# lm3410-boost-flashlight-driver-17mm-mk-1.net
KiCad netlist of a schematic drawn in EAGLE
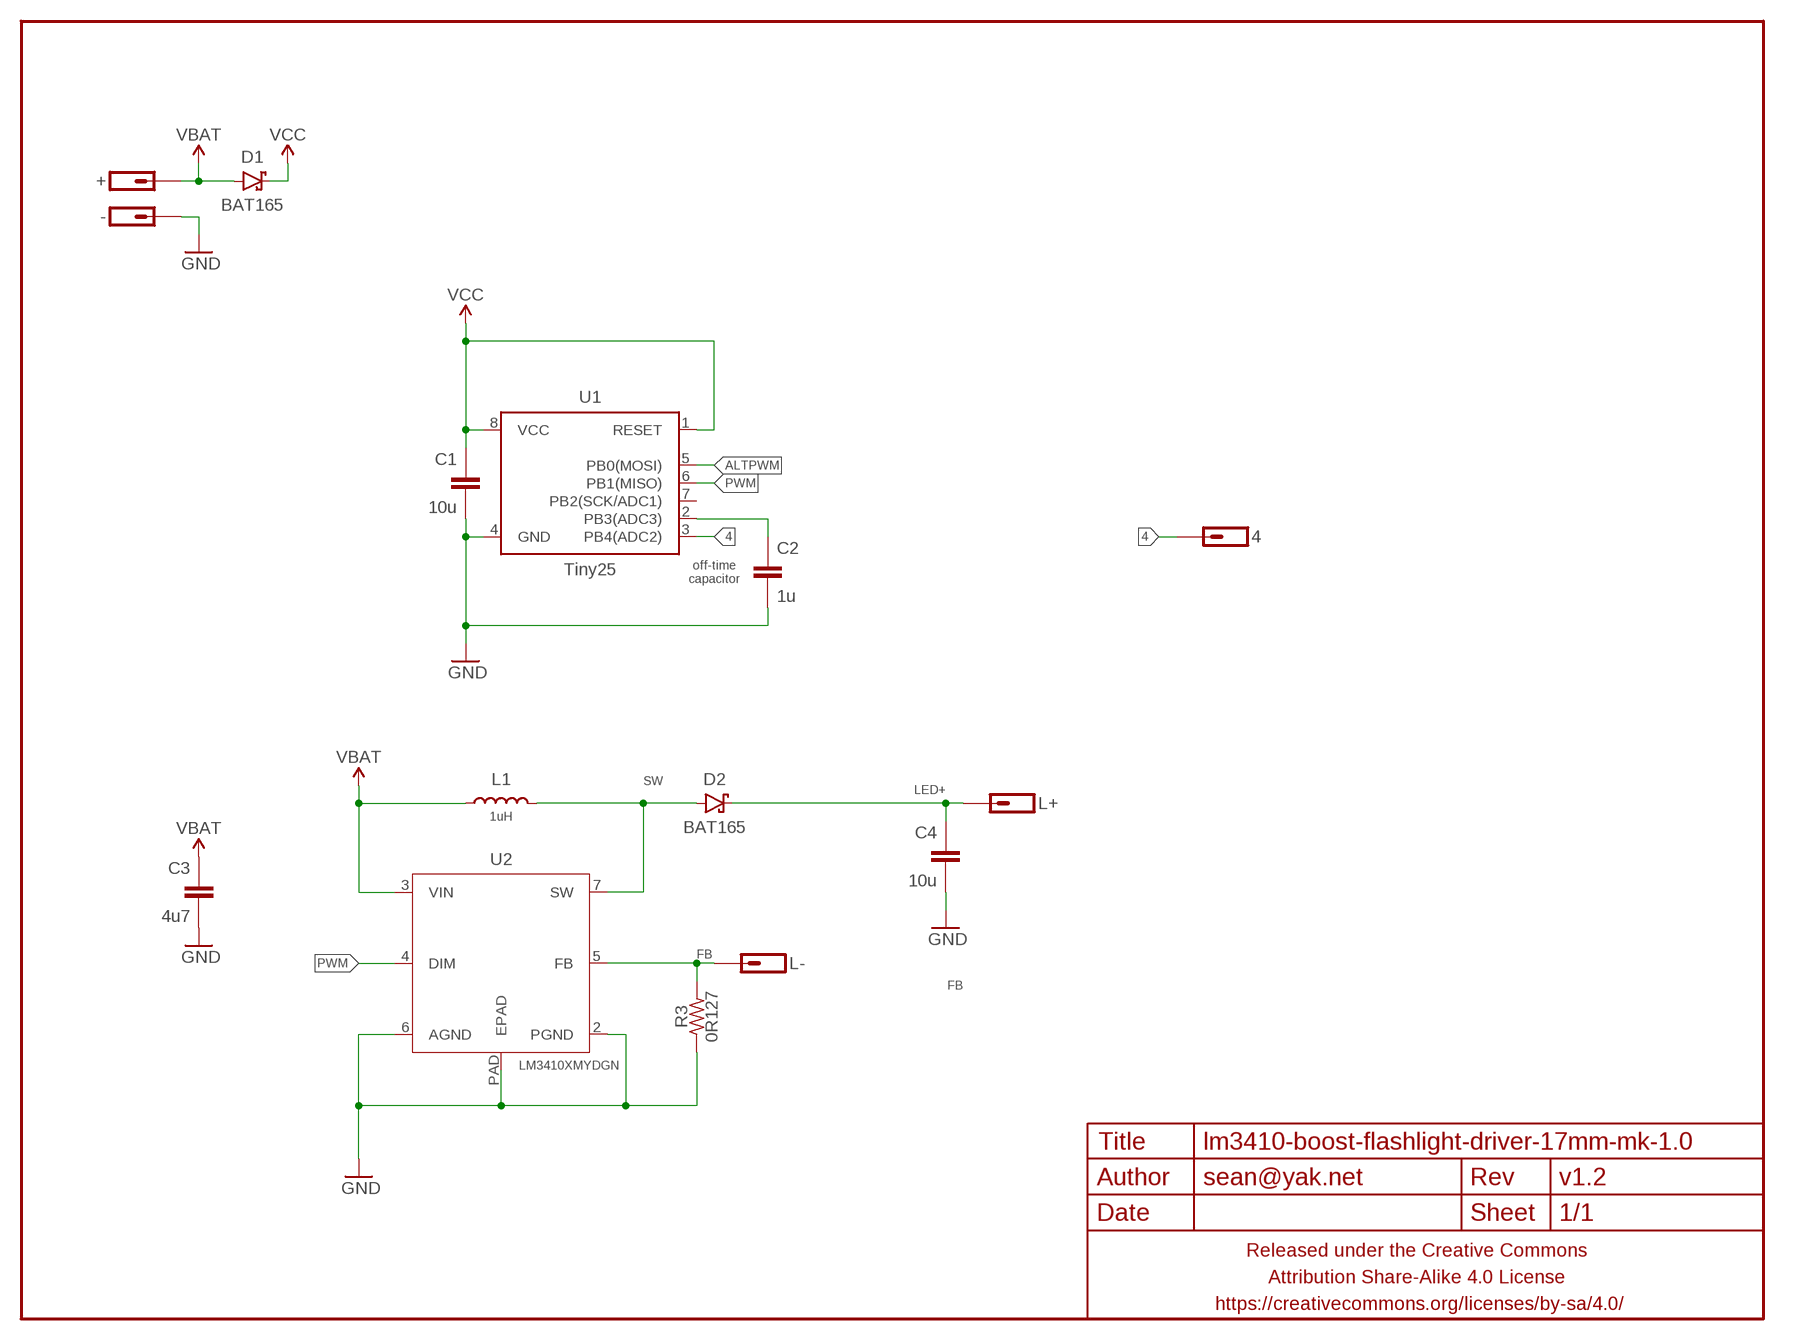
[diagram p0: schematic, sheet 1]

(export (version "E")
  (design (tool "Eeschema 10.0.6"))
  (components
    (comp (ref "+")
      (value "M01PTH-1MM-CIR-NS")
      (footprint "eagle-import:1X01-1MM-CIR-NS")
      (libsource (lib "eagle-import") (part "M01PTH-1MM-CIR-NS"))
    )
    (comp (ref "-")
      (value "M01NOT-A-VIA-NOPE")
      (footprint "eagle-import:1X01_NOSILK_NOSTOP")
      (libsource (lib "eagle-import") (part "M01NOT-A-VIA-NOPE"))
    )
    (comp (ref "4")
      (value "M01SMD-1MM-DIA-NS")
      (footprint "eagle-import:1X01-SMD-1MM-DIA-NS")
      (libsource (lib "eagle-import") (part "M01SMD-1MM-DIA-NS"))
    )
    (comp (ref "C1")
      (value "10u")
      (footprint "eagle-import:C0603-TIGHTER")
      (libsource (lib "eagle-import") (part "CAPACITOR-CERAMICC0603-TIGHTER"))
    )
    (comp (ref "C2")
      (value "1u")
      (footprint "eagle-import:C0603-TIGHTER")
      (libsource (lib "eagle-import") (part "CAPACITOR-CERAMICC0603-TIGHTER"))
    )
    (comp (ref "C3")
      (value "4u7")
      (footprint "eagle-import:C0603-TIGHTER")
      (libsource (lib "eagle-import") (part "CAPACITOR-CERAMICC0603-TIGHTER"))
    )
    (comp (ref "C4")
      (value "10u")
      (footprint "eagle-import:C0603-TIGHTER")
      (libsource (lib "eagle-import") (part "CAPACITOR-CERAMICC0603-TIGHTER"))
    )
    (comp (ref "D1")
      (value "BAT165")
      (footprint "eagle-import:SOD323-SCHOTTKY")
      (libsource (lib "eagle-import") (part "DIODE-SCHOTTKYSOD323"))
    )
    (comp (ref "D2")
      (value "BAT165")
      (footprint "eagle-import:SOD323-SCHOTTKY")
      (libsource (lib "eagle-import") (part "DIODE-SCHOTTKYSOD323"))
    )
    (comp (ref "FRAME1")
      (value "FRAME-LETTERNO_PACKAGE")
      (footprint "eagle-import:DUMMY")
      (fields (field (name "DESIGNER") "sean@yak.net") (field (name "VERSION") "v1.2"))
      (libsource (lib "eagle-import") (part "FRAME-LETTERNO_PACKAGE"))
    )
    (comp (ref "L+")
      (value "M01PTH-1MM-CIR-NS")
      (footprint "eagle-import:1X01-1MM-CIR-NS")
      (libsource (lib "eagle-import") (part "M01PTH-1MM-CIR-NS"))
    )
    (comp (ref "L-")
      (value "M01PTH-1MM-CIR-NS")
      (footprint "eagle-import:1X01-1MM-CIR-NS")
      (libsource (lib "eagle-import") (part "M01PTH-1MM-CIR-NS"))
    )
    (comp (ref "L1")
      (value "1uH")
      (footprint "eagle-import:XFL4020")
      (libsource (lib "eagle-import") (part "INDUCTORXFL4020"))
    )
    (comp (ref "R3")
      (value "0R127")
      (footprint "eagle-import:R0805")
      (libsource (lib "eagle-import") (part "RESISTORR0805"))
    )
    (comp (ref "U1")
      (value "Tiny25")
      (footprint "eagle-import:SO08-SKINNYPADS")
      (libsource (lib "eagle-import") (part "ATTINY45TINY25-SOICN-NARROWER"))
    )
    (comp (ref "U2")
      (value "LM3410XMYDGN")
      (footprint "eagle-import:MSOP-8-PAD-LM3410")
      (libsource (lib "eagle-import") (part "LM3410XMYDGN"))
    )
  )
  (nets
    (net (code "1") (name "/FB") (class "Default")
      (node (ref "L-") (pin "1") (pinfunction "1_1") (pintype "passive"))
      (node (ref "R3") (pin "2") (pinfunction "2_2") (pintype "passive"))
      (node (ref "U2") (pin "5") (pinfunction "FB_5") (pintype "input"))
    )
    (net (code "2") (name "/LED+") (class "Default")
      (node (ref "C4") (pin "1") (pinfunction "1_1") (pintype "passive"))
      (node (ref "D2") (pin "C") (pinfunction "C_C") (pintype "passive"))
      (node (ref "L+") (pin "1") (pinfunction "1_1") (pintype "passive"))
    )
    (net (code "3") (name "/SW") (class "Default")
      (node (ref "D2") (pin "A") (pinfunction "A_A") (pintype "passive"))
      (node (ref "L1") (pin "P$2") (pinfunction "2_P$2") (pintype "passive"))
      (node (ref "U2") (pin "7") (pinfunction "SW_7") (pintype "output"))
    )
    (net (code "4") (name "4") (class "Default")
      (node (ref "4") (pin "P$1") (pinfunction "1_P$1") (pintype "passive"))
      (node (ref "U1") (pin "3") (pinfunction "PB4(ADC2)_3") (pintype "bidirectional"))
    )
    (net (code "5") (name "ALTPWM") (class "Default")
      (node (ref "U1") (pin "5") (pinfunction "PB0(MOSI)_5") (pintype "bidirectional"))
    )
    (net (code "6") (name "GND") (class "Default")
      (node (ref "-") (pin "P$1") (pinfunction "1_P$1") (pintype "passive"))
      (node (ref "C1") (pin "2") (pinfunction "2_2") (pintype "passive"))
      (node (ref "C2") (pin "2") (pinfunction "2_2") (pintype "passive"))
      (node (ref "C3") (pin "2") (pinfunction "2_2") (pintype "passive"))
      (node (ref "C4") (pin "2") (pinfunction "2_2") (pintype "passive"))
      (node (ref "R3") (pin "1") (pinfunction "1_1") (pintype "passive"))
      (node (ref "U1") (pin "4") (pinfunction "GND_4") (pintype "bidirectional"))
      (node (ref "U2") (pin "2") (pinfunction "PGND_2") (pintype "passive"))
      (node (ref "U2") (pin "6") (pinfunction "AGND_6") (pintype "passive"))
      (node (ref "U2") (pin "PAD") (pinfunction "EPAD_PAD") (pintype "passive"))
    )
    (net (code "7") (name "Net-(U1-PB3(ADC3))") (class "Default")
      (node (ref "C2") (pin "1") (pinfunction "1_1") (pintype "passive"))
      (node (ref "U1") (pin "2") (pinfunction "PB3(ADC3)_2") (pintype "bidirectional"))
    )
    (net (code "8") (name "PWM") (class "Default")
      (node (ref "U1") (pin "6") (pinfunction "PB1(MISO)_6") (pintype "bidirectional"))
      (node (ref "U2") (pin "4") (pinfunction "DIM_4") (pintype "input"))
    )
    (net (code "9") (name "VBAT") (class "Default")
      (node (ref "+") (pin "1") (pinfunction "1_1") (pintype "passive"))
      (node (ref "C3") (pin "1") (pinfunction "1_1") (pintype "passive"))
      (node (ref "D1") (pin "A") (pinfunction "A_A") (pintype "passive"))
      (node (ref "L1") (pin "P$1") (pinfunction "1_P$1") (pintype "passive"))
      (node (ref "U2") (pin "3") (pinfunction "VIN_3") (pintype "power_in"))
    )
    (net (code "10") (name "VCC") (class "Default")
      (node (ref "C1") (pin "1") (pinfunction "1_1") (pintype "passive"))
      (node (ref "D1") (pin "C") (pinfunction "C_C") (pintype "passive"))
      (node (ref "U1") (pin "1") (pinfunction "RESET_1") (pintype "bidirectional"))
      (node (ref "U1") (pin "8") (pinfunction "VCC_8") (pintype "bidirectional"))
    )
    (net (code "11") (name "unconnected-(U1-PB2(SCK{slash}ADC1)-Pad7)") (class "Default")
      (node (ref "U1") (pin "7") (pinfunction "PB2(SCK/ADC1)_7") (pintype "bidirectional"))
    )
  )
)
